# SI570_vcxo_draft1.net
KiCad netlist of a schematic drawn in EAGLE
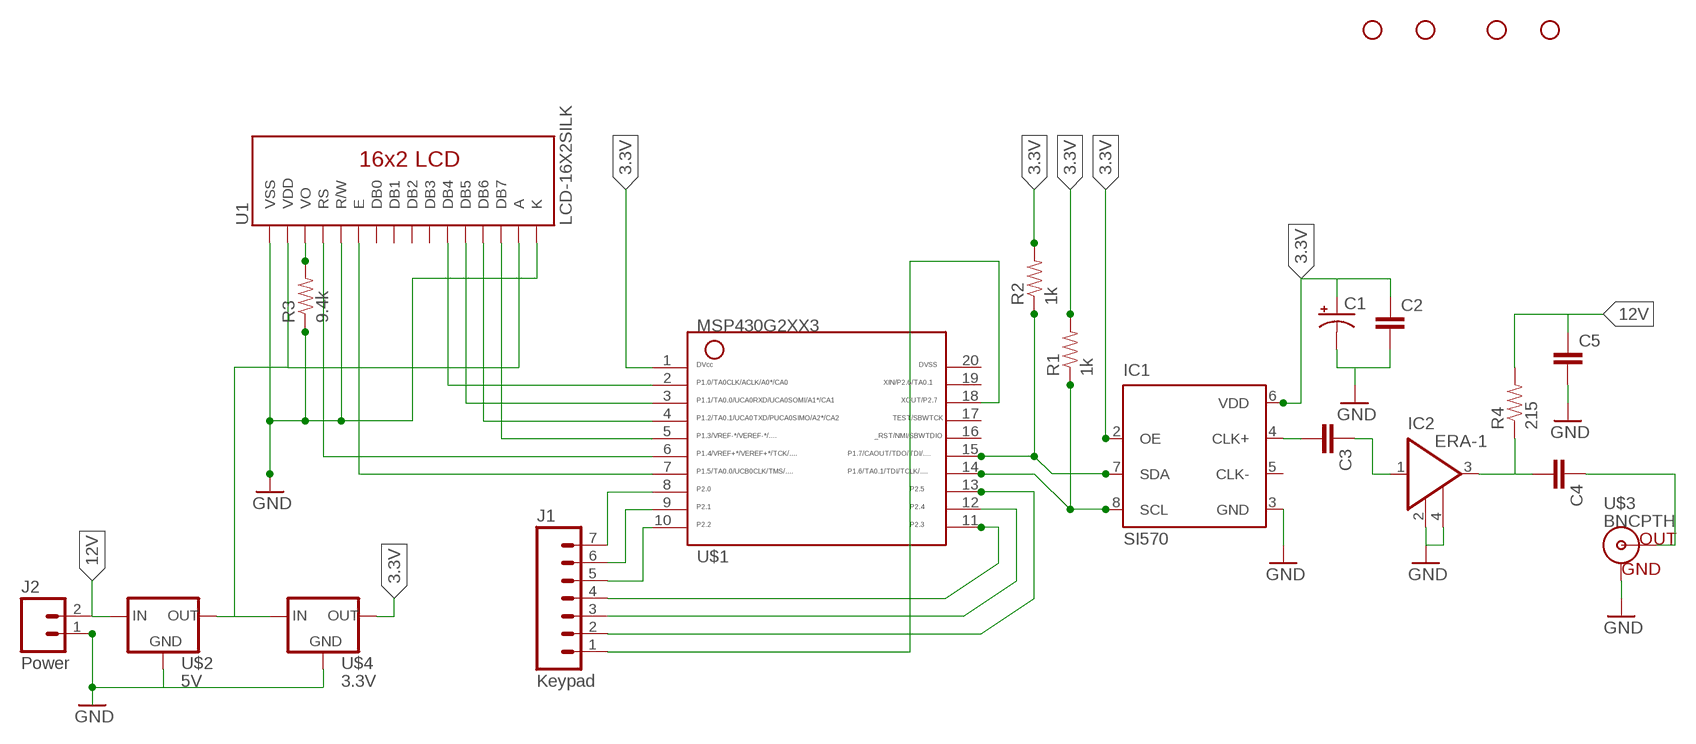
[diagram p0: schematic, sheet 1]

(export (version "E")
  (design (tool "Eeschema 10.0.6"))
  (components
    (comp (ref "C1")
      (value "100UF-25V-20%(PTH)")
      (footprint "eagle-import:CPOL-RADIAL-100UF-25V")
      (libsource (lib "eagle-import") (part "100UF-25V-20%(PTH)"))
    )
    (comp (ref "C2")
      (value "CAP0603-CAP")
      (footprint "eagle-import:0603-CAP")
      (libsource (lib "eagle-import") (part "CAP0603-CAP"))
    )
    (comp (ref "C3")
      (value "CAP0603-CAP")
      (footprint "eagle-import:0603-CAP")
      (libsource (lib "eagle-import") (part "CAP0603-CAP"))
    )
    (comp (ref "C4")
      (value "CAP0603-CAP")
      (footprint "eagle-import:0603-CAP")
      (libsource (lib "eagle-import") (part "CAP0603-CAP"))
    )
    (comp (ref "C5")
      (value "CAP0603-CAP")
      (footprint "eagle-import:0603-CAP")
      (libsource (lib "eagle-import") (part "CAP0603-CAP"))
    )
    (comp (ref "H1")
      (value "STAND-OFF")
      (footprint "eagle-import:STAND-OFF")
      (libsource (lib "eagle-import") (part "STAND-OFF"))
    )
    (comp (ref "H2")
      (value "STAND-OFF")
      (footprint "eagle-import:STAND-OFF")
      (libsource (lib "eagle-import") (part "STAND-OFF"))
    )
    (comp (ref "H3")
      (value "STAND-OFF")
      (footprint "eagle-import:STAND-OFF")
      (libsource (lib "eagle-import") (part "STAND-OFF"))
    )
    (comp (ref "H4")
      (value "STAND-OFF")
      (footprint "eagle-import:STAND-OFF")
      (libsource (lib "eagle-import") (part "STAND-OFF"))
    )
    (comp (ref "IC1")
      (value "SI570")
      (footprint "eagle-import:8-PIN")
      (libsource (lib "eagle-import") (part "SI570"))
    )
    (comp (ref "IC2")
      (value "ERA-1")
      (footprint "eagle-import:VV")
      (libsource (lib "eagle-import") (part "ERA-1"))
    )
    (comp (ref "J1")
      (value "Keypad")
      (footprint "eagle-import:1X07")
      (libsource (lib "eagle-import") (part "M07"))
    )
    (comp (ref "J2")
      (value "Power")
      (footprint "eagle-import:1X02")
      (libsource (lib "eagle-import") (part "M02PTH"))
    )
    (comp (ref "R1")
      (value "1k")
      (footprint "eagle-import:AXIAL-0.3EZ")
      (libsource (lib "eagle-import") (part "RESISTOREZ"))
    )
    (comp (ref "R2")
      (value "1k")
      (footprint "eagle-import:AXIAL-0.3EZ")
      (libsource (lib "eagle-import") (part "RESISTOREZ"))
    )
    (comp (ref "R3")
      (value "9.4k")
      (footprint "eagle-import:AXIAL-0.3EZ")
      (libsource (lib "eagle-import") (part "RESISTOREZ"))
    )
    (comp (ref "R4")
      (value "215")
      (footprint "eagle-import:AXIAL-0.3EZ")
      (libsource (lib "eagle-import") (part "RESISTOREZ"))
    )
    (comp (ref "U$1")
      (value "G2XX3---N20")
      (footprint "eagle-import:N20")
      (libsource (lib "eagle-import") (part "G2XX3---N20"))
    )
    (comp (ref "U$2")
      (value "5V")
      (footprint "eagle-import:LD1117V33")
      (libsource (lib "eagle-import") (part "LD1117V33"))
    )
    (comp (ref "U$3")
      (value "BNCPTH")
      (footprint "eagle-import:BNC")
      (libsource (lib "eagle-import") (part "BNCPTH"))
    )
    (comp (ref "U$4")
      (value "3.3V")
      (footprint "eagle-import:LD1117V33")
      (libsource (lib "eagle-import") (part "LD1117V33"))
    )
    (comp (ref "U1")
      (value "LCD-16X2SILK")
      (footprint "eagle-import:LCD-16X2")
      (libsource (lib "eagle-import") (part "LCD-16X2SILK"))
    )
  )
  (nets
    (net (code "1") (name "3.3V") (class "Default")
      (node (ref "C1") (pin "1") (pinfunction "+_1") (pintype "passive"))
      (node (ref "C2") (pin "1") (pinfunction "1_1") (pintype "passive"))
      (node (ref "IC1") (pin "2") (pinfunction "OE_2") (pintype "input"))
      (node (ref "IC1") (pin "6") (pinfunction "VDD_6") (pintype "power_in"))
      (node (ref "R1") (pin "P$2") (pinfunction "2_P$2") (pintype "passive"))
      (node (ref "R2") (pin "P$2") (pinfunction "2_P$2") (pintype "passive"))
      (node (ref "U$1") (pin "1") (pinfunction "1_1") (pintype "bidirectional"))
      (node (ref "U$4") (pin "OUT") (pinfunction "OUT_OUT") (pintype "output"))
    )
    (net (code "2") (name "12V") (class "Default")
      (node (ref "C5") (pin "1") (pinfunction "1_1") (pintype "passive"))
      (node (ref "J2") (pin "2") (pinfunction "2_2") (pintype "passive"))
      (node (ref "R4") (pin "P$2") (pinfunction "2_P$2") (pintype "passive"))
      (node (ref "U$2") (pin "IN") (pinfunction "IN_IN") (pintype "input"))
    )
    (net (code "3") (name "GND") (class "Default")
      (node (ref "C1") (pin "2") (pinfunction "-_2") (pintype "passive"))
      (node (ref "C2") (pin "2") (pinfunction "2_2") (pintype "passive"))
      (node (ref "C5") (pin "2") (pinfunction "2_2") (pintype "passive"))
      (node (ref "IC1") (pin "3") (pinfunction "GND_3") (pintype "power_in"))
      (node (ref "IC2") (pin "2") (pinfunction "GND_2") (pintype "power_in"))
      (node (ref "IC2") (pin "4") (pinfunction "GND_4") (pintype "power_in"))
      (node (ref "J2") (pin "1") (pinfunction "1_1") (pintype "passive"))
      (node (ref "R3") (pin "P$1") (pinfunction "1_P$1") (pintype "passive"))
      (node (ref "U$2") (pin "GND") (pinfunction "GND_GND") (pintype "input"))
      (node (ref "U$3") (pin "GND") (pinfunction "GND_GND") (pintype "bidirectional"))
      (node (ref "U$4") (pin "GND") (pinfunction "GND_GND") (pintype "input"))
      (node (ref "U1") (pin "1") (pinfunction "VSS_1") (pintype "power_in"))
      (node (ref "U1") (pin "16") (pinfunction "K_16") (pintype "power_in"))
      (node (ref "U1") (pin "5") (pinfunction "R/W_5") (pintype "input"))
    )
    (net (code "4") (name "Net-(IC1-CLK+)") (class "Default")
      (node (ref "C3") (pin "2") (pinfunction "2_2") (pintype "passive"))
      (node (ref "IC1") (pin "4") (pinfunction "CLK+_4") (pintype "output"))
    )
    (net (code "5") (name "Net-(IC1-SCL)") (class "Default")
      (node (ref "IC1") (pin "8") (pinfunction "SCL_8") (pintype "input"))
      (node (ref "R1") (pin "P$1") (pinfunction "1_P$1") (pintype "passive"))
      (node (ref "U$1") (pin "14") (pinfunction "14_14") (pintype "bidirectional"))
    )
    (net (code "6") (name "Net-(IC1-SDA)") (class "Default")
      (node (ref "IC1") (pin "7") (pinfunction "SDA_7") (pintype "input"))
      (node (ref "R2") (pin "P$1") (pinfunction "1_P$1") (pintype "passive"))
      (node (ref "U$1") (pin "15") (pinfunction "15_15") (pintype "bidirectional"))
    )
    (net (code "7") (name "Net-(IC2-RFIN)") (class "Default")
      (node (ref "C3") (pin "1") (pinfunction "1_1") (pintype "passive"))
      (node (ref "IC2") (pin "1") (pinfunction "RFIN_1") (pintype "input"))
    )
    (net (code "8") (name "Net-(IC2-RFOUT{slash}DCIN)") (class "Default")
      (node (ref "C4") (pin "2") (pinfunction "2_2") (pintype "passive"))
      (node (ref "IC2") (pin "3") (pinfunction "RFOUT/DCIN_3") (pintype "output"))
      (node (ref "R4") (pin "P$1") (pinfunction "1_P$1") (pintype "passive"))
    )
    (net (code "9") (name "Net-(J1-Pad1)") (class "Default")
      (node (ref "J1") (pin "1") (pinfunction "1_1") (pintype "passive"))
      (node (ref "U$1") (pin "18") (pinfunction "18_18") (pintype "bidirectional"))
    )
    (net (code "10") (name "Net-(J1-Pad2)") (class "Default")
      (node (ref "J1") (pin "2") (pinfunction "2_2") (pintype "passive"))
      (node (ref "U$1") (pin "13") (pinfunction "13_13") (pintype "bidirectional"))
    )
    (net (code "11") (name "Net-(J1-Pad3)") (class "Default")
      (node (ref "J1") (pin "3") (pinfunction "3_3") (pintype "passive"))
      (node (ref "U$1") (pin "12") (pinfunction "12_12") (pintype "bidirectional"))
    )
    (net (code "12") (name "Net-(J1-Pad4)") (class "Default")
      (node (ref "J1") (pin "4") (pinfunction "4_4") (pintype "passive"))
      (node (ref "U$1") (pin "11") (pinfunction "11_11") (pintype "bidirectional"))
    )
    (net (code "13") (name "Net-(J1-Pad5)") (class "Default")
      (node (ref "J1") (pin "5") (pinfunction "5_5") (pintype "passive"))
      (node (ref "U$1") (pin "10") (pinfunction "10_10") (pintype "bidirectional"))
    )
    (net (code "14") (name "Net-(J1-Pad6)") (class "Default")
      (node (ref "J1") (pin "6") (pinfunction "6_6") (pintype "passive"))
      (node (ref "U$1") (pin "9") (pinfunction "9_9") (pintype "bidirectional"))
    )
    (net (code "15") (name "Net-(J1-Pad7)") (class "Default")
      (node (ref "J1") (pin "7") (pinfunction "7_7") (pintype "passive"))
      (node (ref "U$1") (pin "8") (pinfunction "8_8") (pintype "bidirectional"))
    )
    (net (code "16") (name "Net-(R3-2)") (class "Default")
      (node (ref "R3") (pin "P$2") (pinfunction "2_P$2") (pintype "passive"))
      (node (ref "U1") (pin "3") (pinfunction "VO_3") (pintype "bidirectional"))
    )
    (net (code "17") (name "Net-(U$3-OUT)") (class "Default")
      (node (ref "C4") (pin "1") (pinfunction "1_1") (pintype "passive"))
      (node (ref "U$3") (pin "S") (pinfunction "OUT_S") (pintype "bidirectional"))
    )
    (net (code "18") (name "Net-(U1-A)") (class "Default")
      (node (ref "U$2") (pin "OUT") (pinfunction "OUT_OUT") (pintype "output"))
      (node (ref "U$4") (pin "IN") (pinfunction "IN_IN") (pintype "input"))
      (node (ref "U1") (pin "15") (pinfunction "A_15") (pintype "power_in"))
      (node (ref "U1") (pin "2") (pinfunction "VDD_2") (pintype "power_in"))
    )
    (net (code "19") (name "Net-(U1-DB4)") (class "Default")
      (node (ref "U$1") (pin "2") (pinfunction "2_2") (pintype "bidirectional"))
      (node (ref "U1") (pin "11") (pinfunction "DB4_11") (pintype "bidirectional"))
    )
    (net (code "20") (name "Net-(U1-DB5)") (class "Default")
      (node (ref "U$1") (pin "3") (pinfunction "3_3") (pintype "bidirectional"))
      (node (ref "U1") (pin "12") (pinfunction "DB5_12") (pintype "bidirectional"))
    )
    (net (code "21") (name "Net-(U1-DB6)") (class "Default")
      (node (ref "U$1") (pin "4") (pinfunction "4_4") (pintype "bidirectional"))
      (node (ref "U1") (pin "13") (pinfunction "DB6_13") (pintype "bidirectional"))
    )
    (net (code "22") (name "Net-(U1-DB7)") (class "Default")
      (node (ref "U$1") (pin "5") (pinfunction "5_5") (pintype "bidirectional"))
      (node (ref "U1") (pin "14") (pinfunction "DB7_14") (pintype "bidirectional"))
    )
    (net (code "23") (name "Net-(U1-E)") (class "Default")
      (node (ref "U$1") (pin "7") (pinfunction "7_7") (pintype "bidirectional"))
      (node (ref "U1") (pin "6") (pinfunction "E_6") (pintype "input"))
    )
    (net (code "24") (name "Net-(U1-RS)") (class "Default")
      (node (ref "U$1") (pin "6") (pinfunction "6_6") (pintype "bidirectional"))
      (node (ref "U1") (pin "4") (pinfunction "RS_4") (pintype "input"))
    )
    (net (code "25") (name "unconnected-(IC1-CLK--Pad5)") (class "Default")
      (node (ref "IC1") (pin "5") (pinfunction "CLK-_5") (pintype "output"))
    )
    (net (code "26") (name "unconnected-(U$1-Pad16)") (class "Default")
      (node (ref "U$1") (pin "16") (pinfunction "16_16") (pintype "bidirectional"))
    )
    (net (code "27") (name "unconnected-(U$1-Pad17)") (class "Default")
      (node (ref "U$1") (pin "17") (pinfunction "17_17") (pintype "bidirectional"))
    )
    (net (code "28") (name "unconnected-(U$1-Pad19)") (class "Default")
      (node (ref "U$1") (pin "19") (pinfunction "19_19") (pintype "bidirectional"))
    )
    (net (code "29") (name "unconnected-(U$1-Pad20)") (class "Default")
      (node (ref "U$1") (pin "20") (pinfunction "20_20") (pintype "bidirectional"))
    )
    (net (code "30") (name "unconnected-(U1-DB0-Pad7)") (class "Default")
      (node (ref "U1") (pin "7") (pinfunction "DB0_7") (pintype "bidirectional"))
    )
    (net (code "31") (name "unconnected-(U1-DB1-Pad8)") (class "Default")
      (node (ref "U1") (pin "8") (pinfunction "DB1_8") (pintype "bidirectional"))
    )
    (net (code "32") (name "unconnected-(U1-DB2-Pad9)") (class "Default")
      (node (ref "U1") (pin "9") (pinfunction "DB2_9") (pintype "bidirectional"))
    )
    (net (code "33") (name "unconnected-(U1-DB3-Pad10)") (class "Default")
      (node (ref "U1") (pin "10") (pinfunction "DB3_10") (pintype "bidirectional"))
    )
  )
)
